# DDS_OUT_channel.net
KiCad netlist of a schematic drawn in Altium Designer
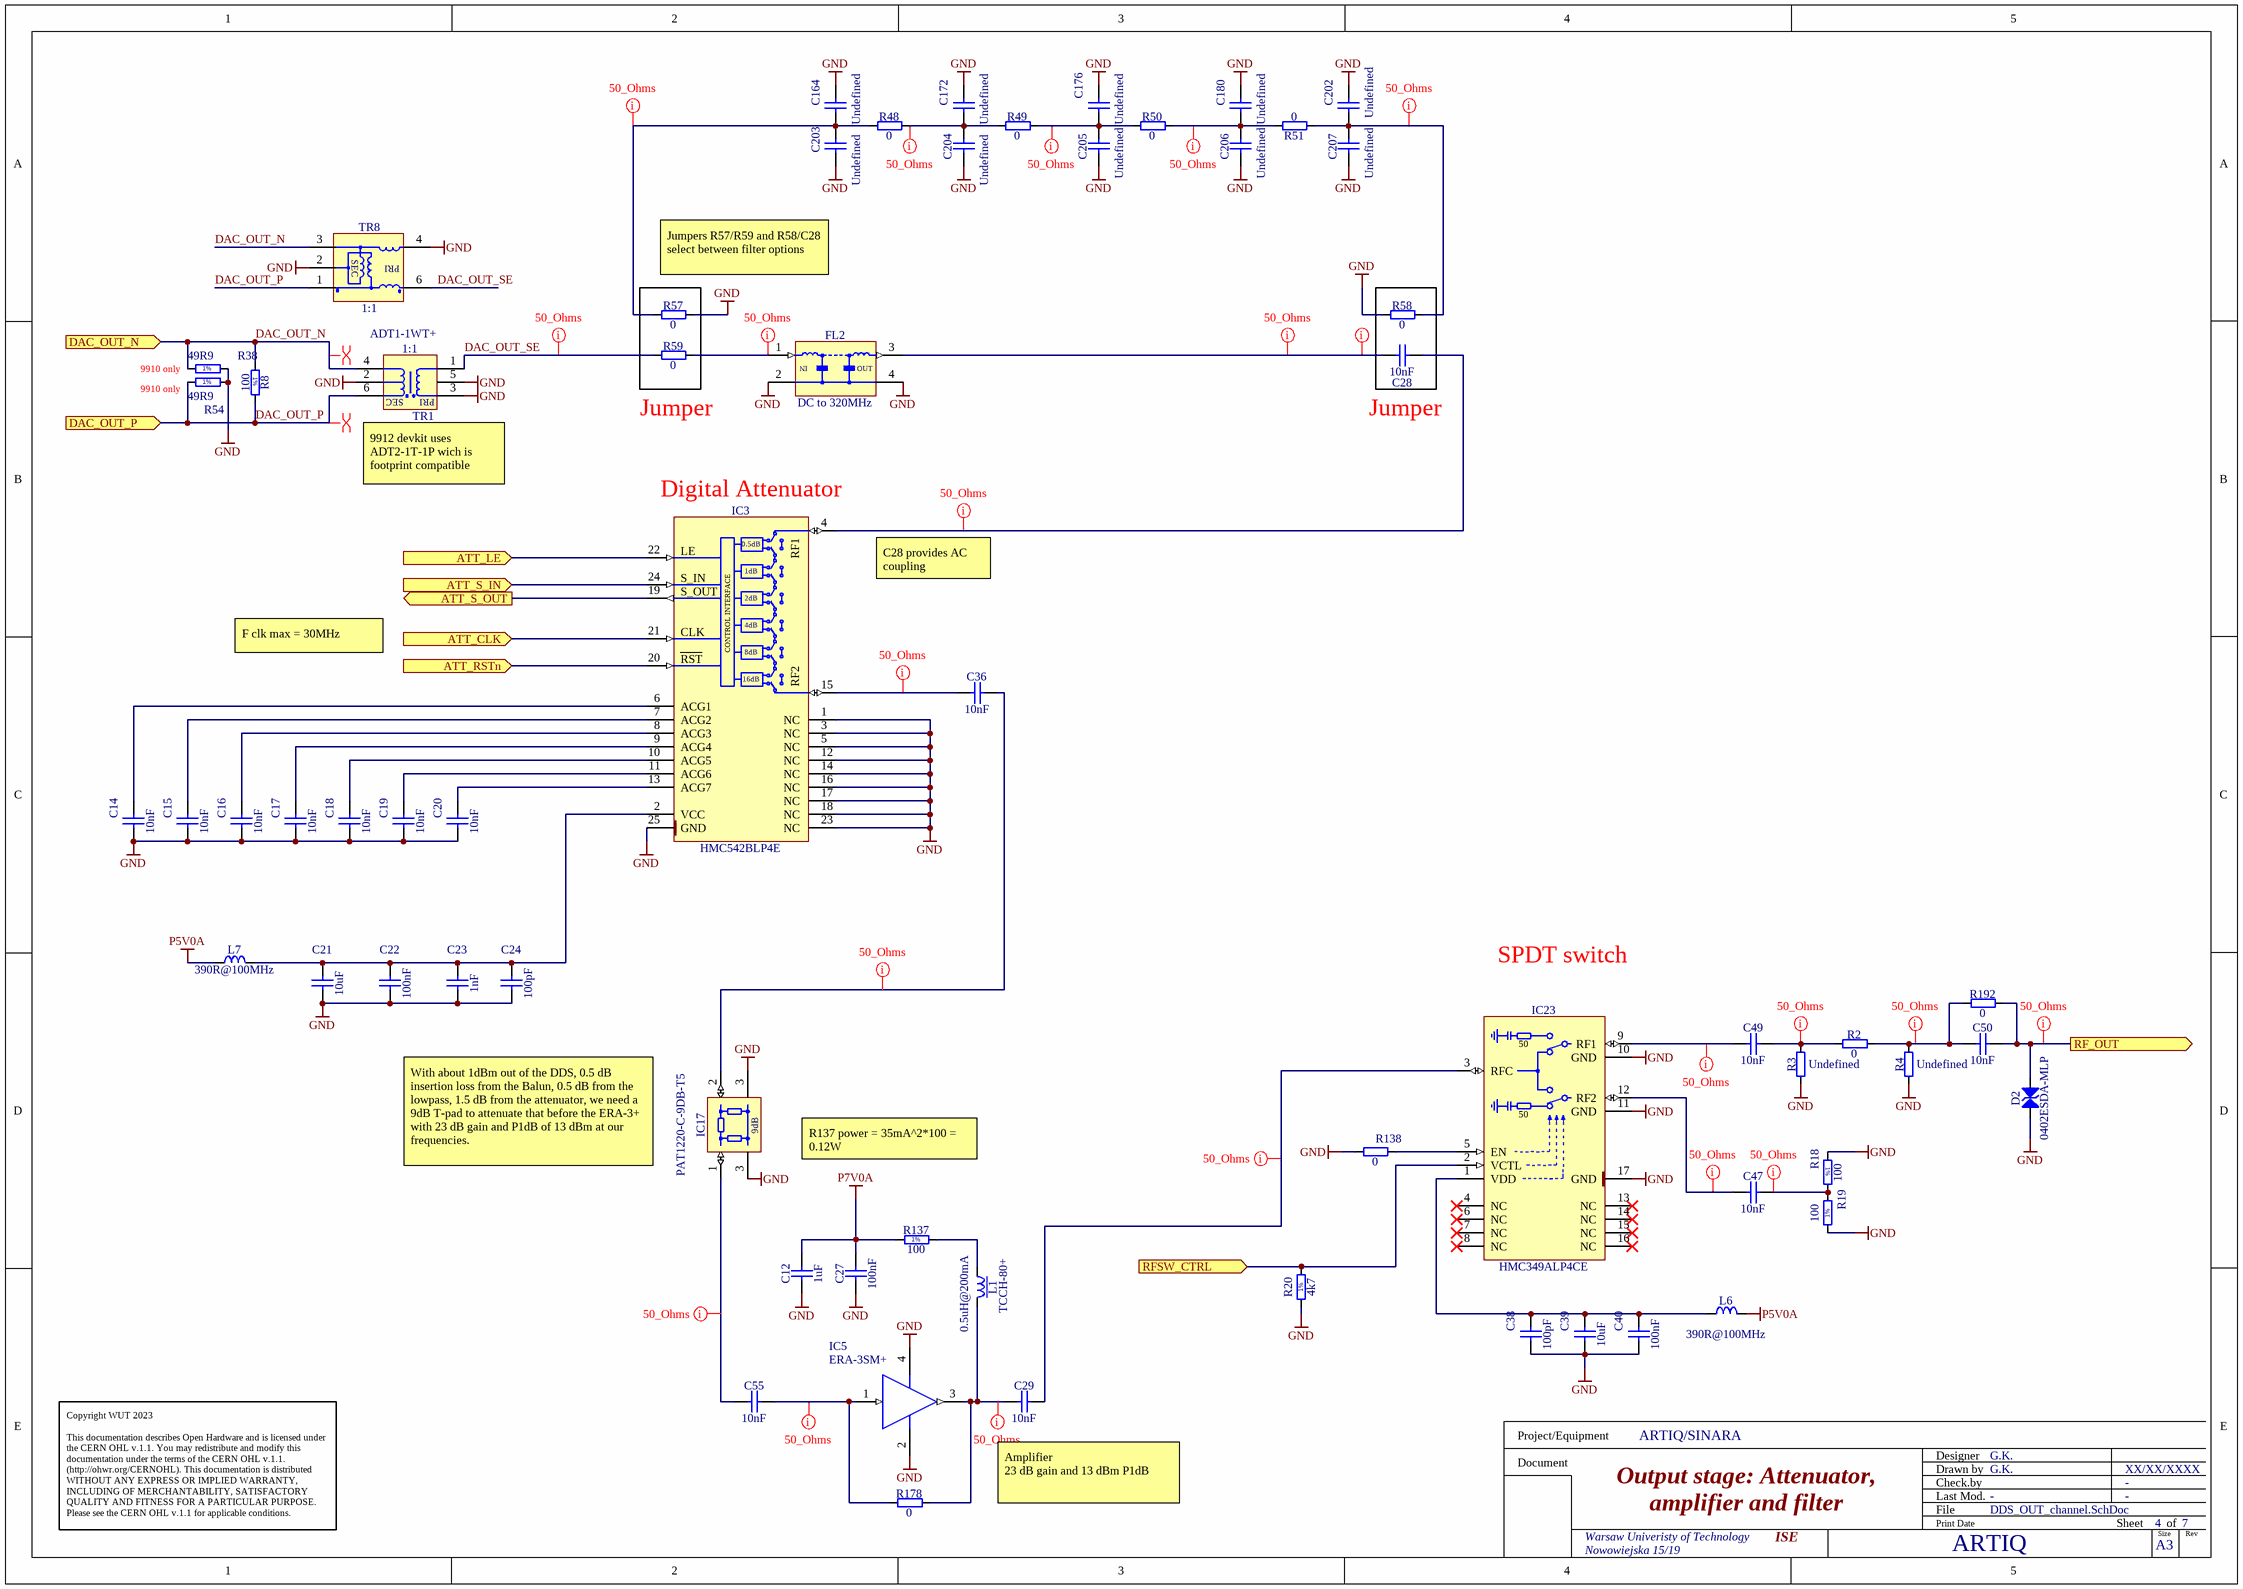
[diagram p0: DDS_OUT_channel.SchDoc]

(export (version "E")
  (design (tool "Eeschema 10.0.6"))
  (components
    (comp (ref "C12")
      (value "1uF")
      (footprint "CAPC2012X140N")
      (description "Non-polarised capacitor")
      (fields
        (field (name "PART NUMBER") "CC0805_1UF_35V_20%_X7R")
        (field (name "VOLTAGE") "35V")
        (field (name "AUTHOR") "CERN DEM JLC")
      )
      (libsource (lib "Capacitors") (part "Capacitor - non polarized"))
    )
    (comp (ref "C14")
      (value "10nF")
      (footprint "CAPC1005X55N")
      (description "Non-polarised capacitor")
      (fields
        (field (name "PART NUMBER") "CC0402_10NF_16V_10%_X7R")
        (field (name "VOLTAGE") "16V")
        (field (name "AUTHOR") "CERN DEM JLC")
      )
      (libsource (lib "Capacitors") (part "Capacitor - non polarized"))
    )
    (comp (ref "C15")
      (value "10nF")
      (footprint "CAPC1005X55N")
      (description "Non-polarised capacitor")
      (fields
        (field (name "PART NUMBER") "CC0402_10NF_16V_10%_X7R")
        (field (name "VOLTAGE") "16V")
        (field (name "AUTHOR") "CERN DEM JLC")
      )
      (libsource (lib "Capacitors") (part "Capacitor - non polarized"))
    )
    (comp (ref "C16")
      (value "10nF")
      (footprint "CAPC1005X55N")
      (description "Non-polarised capacitor")
      (fields
        (field (name "PART NUMBER") "CC0402_10NF_16V_10%_X7R")
        (field (name "VOLTAGE") "16V")
        (field (name "AUTHOR") "CERN DEM JLC")
      )
      (libsource (lib "Capacitors") (part "Capacitor - non polarized"))
    )
    (comp (ref "C17")
      (value "10nF")
      (footprint "CAPC1005X55N")
      (description "Non-polarised capacitor")
      (fields
        (field (name "PART NUMBER") "CC0402_10NF_16V_10%_X7R")
        (field (name "VOLTAGE") "16V")
        (field (name "AUTHOR") "CERN DEM JLC")
      )
      (libsource (lib "Capacitors") (part "Capacitor - non polarized"))
    )
    (comp (ref "C18")
      (value "10nF")
      (footprint "CAPC1005X55N")
      (description "Non-polarised capacitor")
      (fields
        (field (name "PART NUMBER") "CC0402_10NF_16V_10%_X7R")
        (field (name "VOLTAGE") "16V")
        (field (name "AUTHOR") "CERN DEM JLC")
      )
      (libsource (lib "Capacitors") (part "Capacitor - non polarized"))
    )
    (comp (ref "C19")
      (value "10nF")
      (footprint "CAPC1005X55N")
      (description "Non-polarised capacitor")
      (fields
        (field (name "PART NUMBER") "CC0402_10NF_16V_10%_X7R")
        (field (name "VOLTAGE") "16V")
        (field (name "AUTHOR") "CERN DEM JLC")
      )
      (libsource (lib "Capacitors") (part "Capacitor - non polarized"))
    )
    (comp (ref "C20")
      (value "10nF")
      (footprint "CAPC1005X55N")
      (description "Non-polarised capacitor")
      (fields
        (field (name "PART NUMBER") "CC0402_10NF_16V_10%_X7R")
        (field (name "VOLTAGE") "16V")
        (field (name "AUTHOR") "CERN DEM JLC")
      )
      (libsource (lib "Capacitors") (part "Capacitor - non polarized"))
    )
    (comp (ref "C21")
      (value "10uF")
      (footprint "CAPC1608X80N")
      (description "Non-polarised capacitor")
      (fields
        (field (name "PART NUMBER") "CC0603_10UF_16V_20%_X5R")
        (field (name "VOLTAGE") "16V")
        (field (name "AUTHOR") "CERN DEM MR")
      )
      (libsource (lib "Capacitors") (part "Capacitor - non polarized"))
    )
    (comp (ref "C22")
      (value "100nF")
      (footprint "CAPC1005X55N")
      (description "Non-polarised capacitor")
      (fields
        (field (name "PART NUMBER") "CC0402_100NF_16V_10%_X7R")
        (field (name "VOLTAGE") "16V")
        (field (name "AUTHOR") "CERN DEM JLC")
      )
      (libsource (lib "Capacitors") (part "Capacitor - non polarized"))
    )
    (comp (ref "C23")
      (value "1nF")
      (footprint "CAPC1005X55N")
      (description "Non-polarised capacitor")
      (fields
        (field (name "PART NUMBER") "CC0402_1NF_50V_10%_X7R")
        (field (name "VOLTAGE") "50V")
        (field (name "AUTHOR") "CERN DEM JLC")
      )
      (libsource (lib "Capacitors") (part "Capacitor - non polarized"))
    )
    (comp (ref "C24")
      (value "100pF")
      (footprint "CAPC1005X55N")
      (description "Non-polarised capacitor")
      (fields
        (field (name "PART NUMBER") "CC0402_100PF_50V_5%_C0G")
        (field (name "VOLTAGE") "50V")
        (field (name "AUTHOR") "CERN DEM JLC")
      )
      (libsource (lib "Capacitors") (part "Capacitor - non polarized"))
    )
    (comp (ref "C27")
      (value "100nF")
      (footprint "CAPC1005X55N")
      (description "Non-polarised capacitor")
      (fields
        (field (name "PART NUMBER") "CC0402_100NF_16V_10%_X5R")
        (field (name "VOLTAGE") "16V")
        (field (name "AUTHOR") "CERN DEM JLC")
      )
      (libsource (lib "Capacitors") (part "Capacitor - non polarized"))
    )
    (comp (ref "C28")
      (value "10nF")
      (footprint "CAPC1005X55N")
      (description "Non-polarised capacitor")
      (fields
        (field (name "PART NUMBER") "CC0402_10NF_16V_10%_X7R")
        (field (name "VOLTAGE") "16V")
        (field (name "AUTHOR") "CERN DEM JLC")
      )
      (libsource (lib "Capacitors") (part "Capacitor - non polarized"))
    )
    (comp (ref "C29")
      (value "10nF")
      (footprint "CAPC1005X55N")
      (description "Non-polarised capacitor")
      (fields
        (field (name "PART NUMBER") "CC0402_10NF_16V_10%_X7R")
        (field (name "VOLTAGE") "16V")
        (field (name "AUTHOR") "CERN DEM JLC")
      )
      (libsource (lib "Capacitors") (part "Capacitor - non polarized"))
    )
    (comp (ref "C36")
      (value "10nF")
      (footprint "CAPC1005X55N")
      (description "Non-polarised capacitor")
      (fields
        (field (name "PART NUMBER") "CC0402_10NF_16V_10%_X7R")
        (field (name "VOLTAGE") "16V")
        (field (name "AUTHOR") "CERN DEM JLC")
      )
      (libsource (lib "Capacitors") (part "Capacitor - non polarized"))
    )
    (comp (ref "C38")
      (value "100pF")
      (footprint "CAPC1005X55N")
      (description "Non-polarised capacitor")
      (fields
        (field (name "PART NUMBER") "CC0402_100PF_50V_5%_C0G")
        (field (name "VOLTAGE") "50V")
        (field (name "AUTHOR") "CERN DEM JLC")
      )
      (libsource (lib "Capacitors") (part "Capacitor - non polarized"))
    )
    (comp (ref "C39")
      (value "10uF")
      (footprint "CAPC1608X80N")
      (description "Non-polarised capacitor")
      (fields
        (field (name "PART NUMBER") "CC0603_10UF_16V_20%_X5R")
        (field (name "VOLTAGE") "16V")
        (field (name "AUTHOR") "CERN DEM MR")
      )
      (libsource (lib "Capacitors") (part "Capacitor - non polarized"))
    )
    (comp (ref "C40")
      (value "100nF")
      (footprint "CAPC1005X55N")
      (description "Non-polarised capacitor")
      (fields
        (field (name "PART NUMBER") "CC0402_100NF_16V_10%_X5R")
        (field (name "VOLTAGE") "16V")
        (field (name "AUTHOR") "CERN DEM JLC")
      )
      (libsource (lib "Capacitors") (part "Capacitor - non polarized"))
    )
    (comp (ref "C47")
      (value "10nF")
      (footprint "CAPC1005X55N")
      (description "Non-polarised capacitor")
      (fields
        (field (name "PART NUMBER") "CC0402_10NF_16V_10%_X7R")
        (field (name "VOLTAGE") "16V")
        (field (name "AUTHOR") "CERN DEM JLC")
      )
      (libsource (lib "Capacitors") (part "Capacitor - non polarized"))
    )
    (comp (ref "C49")
      (value "10nF")
      (footprint "CAPC1005X55N")
      (description "Non-polarised capacitor")
      (fields
        (field (name "PART NUMBER") "CC0402_10NF_16V_10%_X7R")
        (field (name "VOLTAGE") "16V")
        (field (name "AUTHOR") "CERN DEM JLC")
      )
      (libsource (lib "Capacitors") (part "Capacitor - non polarized"))
    )
    (comp (ref "C50")
      (value "10nF")
      (footprint "CAPC1005X55N")
      (description "Non-polarised capacitor")
      (fields
        (field (name "PART NUMBER") "CC0402_10NF_16V_10%_X7R")
        (field (name "VOLTAGE") "16V")
        (field (name "AUTHOR") "CERN DEM JLC")
      )
      (libsource (lib "Capacitors") (part "Capacitor - non polarized"))
    )
    (comp (ref "C55")
      (value "10nF")
      (footprint "CAPC1005X55N")
      (description "Non-polarised capacitor")
      (fields
        (field (name "PART NUMBER") "CC0402_10NF_16V_10%_X7R")
        (field (name "VOLTAGE") "16V")
        (field (name "AUTHOR") "CERN DEM JLC")
      )
      (libsource (lib "Capacitors") (part "Capacitor - non polarized"))
    )
    (comp (ref "C164")
      (value "Undefined")
      (footprint "CAPC1005X55N")
      (description "Non-polarised capacitor")
      (fields (field (name "PART NUMBER") "CC0402_NO-VALUE") (field (name "AUTHOR") "CERN DEM JLC"))
      (libsource (lib "Capacitors") (part "Capacitor - non polarized"))
    )
    (comp (ref "C172")
      (value "Undefined")
      (footprint "CAPC1005X55N")
      (description "Non-polarised capacitor")
      (fields (field (name "PART NUMBER") "CC0402_NO-VALUE") (field (name "AUTHOR") "CERN DEM JLC"))
      (libsource (lib "Capacitors") (part "Capacitor - non polarized"))
    )
    (comp (ref "C176")
      (value "Undefined")
      (footprint "CAPC1005X55N")
      (description "Non-polarised capacitor")
      (fields (field (name "PART NUMBER") "CC0402_NO-VALUE") (field (name "AUTHOR") "CERN DEM JLC"))
      (libsource (lib "Capacitors") (part "Capacitor - non polarized"))
    )
    (comp (ref "C180")
      (value "Undefined")
      (footprint "CAPC1005X55N")
      (description "Non-polarised capacitor")
      (fields (field (name "PART NUMBER") "CC0402_NO-VALUE") (field (name "AUTHOR") "CERN DEM JLC"))
      (libsource (lib "Capacitors") (part "Capacitor - non polarized"))
    )
    (comp (ref "C202")
      (value "Undefined")
      (footprint "CAPC1005X55N")
      (description "Non-polarised capacitor")
      (fields (field (name "PART NUMBER") "CC0402_NO-VALUE") (field (name "AUTHOR") "CERN DEM JLC"))
      (libsource (lib "Capacitors") (part "Capacitor - non polarized"))
    )
    (comp (ref "C203")
      (value "Undefined")
      (footprint "CAPC1005X55N")
      (description "Non-polarised capacitor")
      (fields (field (name "PART NUMBER") "CC0402_NO-VALUE") (field (name "AUTHOR") "CERN DEM JLC"))
      (libsource (lib "Capacitors") (part "Capacitor - non polarized"))
    )
    (comp (ref "C204")
      (value "Undefined")
      (footprint "CAPC1005X55N")
      (description "Non-polarised capacitor")
      (fields (field (name "PART NUMBER") "CC0402_NO-VALUE") (field (name "AUTHOR") "CERN DEM JLC"))
      (libsource (lib "Capacitors") (part "Capacitor - non polarized"))
    )
    (comp (ref "C205")
      (value "Undefined")
      (footprint "CAPC1005X55N")
      (description "Non-polarised capacitor")
      (fields (field (name "PART NUMBER") "CC0402_NO-VALUE") (field (name "AUTHOR") "CERN DEM JLC"))
      (libsource (lib "Capacitors") (part "Capacitor - non polarized"))
    )
    (comp (ref "C206")
      (value "Undefined")
      (footprint "CAPC1005X55N")
      (description "Non-polarised capacitor")
      (fields (field (name "PART NUMBER") "CC0402_NO-VALUE") (field (name "AUTHOR") "CERN DEM JLC"))
      (libsource (lib "Capacitors") (part "Capacitor - non polarized"))
    )
    (comp (ref "C207")
      (value "Undefined")
      (footprint "CAPC1005X55N")
      (description "Non-polarised capacitor")
      (fields (field (name "PART NUMBER") "CC0402_NO-VALUE") (field (name "AUTHOR") "CERN DEM JLC"))
      (libsource (lib "Capacitors") (part "Capacitor - non polarized"))
    )
    (comp (ref "D2")
      (value "0402ESDA-MLP")
      (footprint "EATON_0402ESDA-MLP")
      (description "Transient Voltage Suppressor Diode (Bi-Directional)")
      (fields
        (field (name "VOLTAGE") "8kV")
        (field (name "MANUFACTURER") "EATON")
        (field (name "AUTHOR") "CERN DEM MR")
      )
      (libsource (lib "ICs And Semiconductors") (part "Diode TVS Bi-Directional"))
    )
    (comp (ref "FL2")
      (value "DC to 320MHz")
      (footprint "FIL_MINI-CIRCUITS_FV1206")
      (description "50 Ohm DC to 320MHz Low Pass Filter")
      (fields
        (field (name "PART NUMBER") "FIL_MINI-CIRCUITS_LFCN-320")
        (field (name "MANUFACTURER") "MINI-CIRCUITS")
        (field (name "AUTHOR") "CERN DEM JLC")
      )
      (libsource (lib "LIBRARY_SCH") (part "FIL_MINI-CIRCUITS_LFCN-320"))
    )
    (comp (ref "IC3")
      (value "HMC542BLP4E")
      (footprint "QFN50P400X400X100-25N-S295")
      (description "0.5dB LSB GaAs MMIC 6-bit Digital Serial Control Attenuator, DC - 4GHz")
      (fields (field (name "MANUFACTURER") "HITTITE MICROWAVE CORP") (field (name "AUTHOR") "CERN DEM JMW"))
      (libsource (lib "ICs And Semiconductors") (part "HMC542BLP4E"))
    )
    (comp (ref "IC5")
      (value "ERA-3SM+")
      (footprint "MINI-CIRCUITS_WW107")
      (description "DC-3GHz Monolithic Amplifier")
      (fields (field (name "MANUFACTURER") "MINI-CIRCUITS") (field (name "AUTHOR") "GK"))
      (libsource (lib "LIBRARY_SCH") (part "RF_ERA-3SM+"))
    )
    (comp (ref "IC17")
      (value "PAT1220-C-9DB-T5")
      (footprint "SUSUMU_PAT1220")
      (description "DC to 10GHz, 100mw, 50 Ohm, 9dB, Precision chip attenuator")
      (fields (field (name "MANUFACTURER") "SUSUMU") (field (name "AUTHOR") "GK"))
      (libsource (lib "LIBRARY_SCH") (part "RF_PAT1220-C-9DB-T5"))
    )
    (comp (ref "IC23")
      (value "HMC349ALP4CE")
      (footprint "QFN65P400X400X100-17N-S255")
      (description "DC-4GHz High Isolation SPDT Non-Reflective Switch")
      (fields (field (name "MANUFACTURER") "ANALOG DEVICES") (field (name "AUTHOR") "CERN DEM JLC"))
      (libsource (lib "ICs And Semiconductors") (part "HMC349ALP4CE"))
    )
    (comp (ref "L1")
      (value "0.5uH@200mA")
      (footprint "IND_MINI-CIRCUITS_GU1604")
      (description "50 Ohms, 50 to 8200 MHz RF Choke")
      (fields
        (field (name "PART NUMBER") "IND_MINI-CIRCUITS_TCCH-80+")
        (field (name "POWER") "200mA")
        (field (name "MANUFACTURER PART NUMBER") "TCCH-80+")
        (field (name "AUTHOR") "CERN DEM JLC")
      )
      (libsource (lib "Inductors & Transformers") (part "IND_MINI-CIRCUITS_TCCH-80+"))
    )
    (comp (ref "L6")
      (value "390R@100MHz")
      (footprint "INDC1608X95N")
      (description "Inductor")
      (fields
        (field (name "PART NUMBER") "IND0603_TDK_MPZ1608R391A")
        (field (name "POWER") "1.2A")
        (field (name "AUTHOR") "CERN DEM JLC")
      )
      (libsource (lib "Inductors & Transformers") (part "Inductor"))
    )
    (comp (ref "L7")
      (value "390R@100MHz")
      (footprint "INDC1608X95N")
      (description "Inductor")
      (fields
        (field (name "PART NUMBER") "IND0603_TDK_MPZ1608R391A")
        (field (name "POWER") "1.2A")
        (field (name "AUTHOR") "CERN DEM JLC")
      )
      (libsource (lib "Inductors & Transformers") (part "Inductor"))
    )
    (comp (ref "R2")
      (value "0")
      (footprint "RESC1005X40N")
      (description "Resistor")
      (fields
        (field (name "PART NUMBER") "R0402_0R_JUMPER")
        (field (name "MANUFACTURER") "GENERIC")
        (field (name "AUTHOR") "CERN DEM JLC")
      )
      (libsource (lib "Resistors") (part "Resistor"))
    )
    (comp (ref "R3")
      (value "Undefined")
      (footprint "RESC1005X40N")
      (description "Resistor")
      (fields (field (name "PART NUMBER") "R0402_NO-VALUE") (field (name "AUTHOR") "CERN DEM JLC"))
      (libsource (lib "Resistors") (part "Resistor"))
    )
    (comp (ref "R4")
      (value "Undefined")
      (footprint "RESC1005X40N")
      (description "Resistor")
      (fields (field (name "PART NUMBER") "R0402_NO-VALUE") (field (name "AUTHOR") "CERN DEM JLC"))
      (libsource (lib "Resistors") (part "Resistor"))
    )
    (comp (ref "R8")
      (value "100")
      (footprint "RESC1005X40N")
      (description "Resistor - 1%")
      (fields
        (field (name "PART NUMBER") "R0402_100R_1%_0.0625W_100PPM")
        (field (name "POWER") "0.0625W")
        (field (name "AUTHOR") "CERN DEM JLC")
      )
      (libsource (lib "Resistors") (part "Resistor - 1%"))
    )
    (comp (ref "R18")
      (value "100")
      (footprint "RESC1005X40N")
      (description "Resistor - 1%")
      (fields
        (field (name "PART NUMBER") "R0402_100R_1%_0.0625W_100PPM")
        (field (name "POWER") "0.0625W")
        (field (name "AUTHOR") "CERN DEM JLC")
      )
      (libsource (lib "Resistors") (part "Resistor - 1%"))
    )
    (comp (ref "R19")
      (value "100")
      (footprint "RESC1005X40N")
      (description "Resistor - 1%")
      (fields
        (field (name "PART NUMBER") "R0402_100R_1%_0.0625W_100PPM")
        (field (name "POWER") "0.0625W")
        (field (name "AUTHOR") "CERN DEM JLC")
      )
      (libsource (lib "Resistors") (part "Resistor - 1%"))
    )
    (comp (ref "R20")
      (value "4k7")
      (footprint "RESC1005X40N")
      (description "Resistor - 1%")
      (fields
        (field (name "PART NUMBER") "R0402_4K7_1%_0.0625W_100PPM")
        (field (name "POWER") "0.0625W")
        (field (name "AUTHOR") "CERN DEM JLC")
      )
      (libsource (lib "Resistors") (part "Resistor - 1%"))
    )
    (comp (ref "R38")
      (value "49R9")
      (footprint "RESC1005X40N")
      (description "Resistor - 1%")
      (fields
        (field (name "PART NUMBER") "R0402_49R9_1%_0.0625W_100PPM")
        (field (name "POWER") "0.0625W")
        (field (name "AUTHOR") "CERN DEM JLC")
      )
      (libsource (lib "Resistors") (part "Resistor - 1%"))
    )
    (comp (ref "R48")
      (value "0")
      (footprint "RESC1005X40N")
      (description "Resistor")
      (fields
        (field (name "PART NUMBER") "R0402_0R_JUMPER")
        (field (name "MANUFACTURER") "GENERIC")
        (field (name "AUTHOR") "CERN DEM JLC")
      )
      (libsource (lib "Resistors") (part "Resistor"))
    )
    (comp (ref "R49")
      (value "0")
      (footprint "RESC1005X40N")
      (description "Resistor")
      (fields
        (field (name "PART NUMBER") "R0402_0R_JUMPER")
        (field (name "MANUFACTURER") "GENERIC")
        (field (name "AUTHOR") "CERN DEM JLC")
      )
      (libsource (lib "Resistors") (part "Resistor"))
    )
    (comp (ref "R50")
      (value "0")
      (footprint "RESC1005X40N")
      (description "Resistor")
      (fields
        (field (name "PART NUMBER") "R0402_0R_JUMPER")
        (field (name "MANUFACTURER") "GENERIC")
        (field (name "AUTHOR") "CERN DEM JLC")
      )
      (libsource (lib "Resistors") (part "Resistor"))
    )
    (comp (ref "R51")
      (value "0")
      (footprint "RESC1005X40N")
      (description "Resistor")
      (fields
        (field (name "PART NUMBER") "R0402_0R_JUMPER")
        (field (name "MANUFACTURER") "GENERIC")
        (field (name "AUTHOR") "CERN DEM JLC")
      )
      (libsource (lib "Resistors") (part "Resistor"))
    )
    (comp (ref "R54")
      (value "49R9")
      (footprint "RESC1005X40N")
      (description "Resistor - 1%")
      (fields
        (field (name "PART NUMBER") "R0402_49R9_1%_0.0625W_100PPM")
        (field (name "POWER") "0.0625W")
        (field (name "AUTHOR") "CERN DEM JLC")
      )
      (libsource (lib "Resistors") (part "Resistor - 1%"))
    )
    (comp (ref "R57")
      (value "0")
      (footprint "RESC1005X40N")
      (description "Resistor")
      (fields
        (field (name "PART NUMBER") "R0402_0R_JUMPER")
        (field (name "MANUFACTURER") "GENERIC")
        (field (name "AUTHOR") "CERN DEM JLC")
      )
      (libsource (lib "Resistors") (part "Resistor"))
    )
    (comp (ref "R58")
      (value "0")
      (footprint "RESC1005X40N")
      (description "Resistor")
      (fields
        (field (name "PART NUMBER") "R0402_0R_JUMPER")
        (field (name "MANUFACTURER") "GENERIC")
        (field (name "AUTHOR") "CERN DEM JLC")
      )
      (libsource (lib "Resistors") (part "Resistor"))
    )
    (comp (ref "R59")
      (value "0")
      (footprint "RESC1005X40N")
      (description "Resistor")
      (fields
        (field (name "PART NUMBER") "R0402_0R_JUMPER")
        (field (name "MANUFACTURER") "GENERIC")
        (field (name "AUTHOR") "CERN DEM JLC")
      )
      (libsource (lib "Resistors") (part "Resistor"))
    )
    (comp (ref "R137")
      (value "100")
      (footprint "RESC3216X65N")
      (description "Resistor - 1%")
      (fields
        (field (name "PART NUMBER") "R1206_100R_1%_0.5W_100PPM_VISHAY_CRCW-HP e3")
        (field (name "POWER") "0.5W")
        (field (name "AUTHOR") "CERN DEM JLC")
      )
      (libsource (lib "Resistors") (part "Resistor - 1%"))
    )
    (comp (ref "R138")
      (value "0")
      (footprint "RESC1005X40N")
      (description "Resistor")
      (fields
        (field (name "PART NUMBER") "R0402_0R_JUMPER")
        (field (name "MANUFACTURER") "GENERIC")
        (field (name "AUTHOR") "CERN DEM JLC")
      )
      (libsource (lib "Resistors") (part "Resistor"))
    )
    (comp (ref "R178")
      (value "0")
      (footprint "RESC1608X55N")
      (description "Resistor")
      (fields
        (field (name "PART NUMBER") "R0603_0R_JUMPER")
        (field (name "MANUFACTURER") "GENERIC")
        (field (name "AUTHOR") "CERN DEM JLC")
      )
      (libsource (lib "Resistors") (part "Resistor"))
    )
    (comp (ref "R192")
      (value "0")
      (footprint "RESC1005X40N")
      (description "Resistor")
      (fields
        (field (name "PART NUMBER") "R0402_0R_JUMPER")
        (field (name "MANUFACTURER") "GENERIC")
        (field (name "AUTHOR") "CERN DEM JLC")
      )
      (libsource (lib "Resistors") (part "Resistor"))
    )
    (comp (ref "TR1")
      (value "1:1")
      (footprint "XFMR_MINI-CIRCUITS_CD542")
      (description "75 Ohm 0.4 To 800MHz RF Transformers")
      (fields
        (field (name "PART NUMBER") "XFMR_MINI-CIRCUITS_ADT1-1WT+")
        (field (name "MANUFACTURER") "MINI-CIRCUITS")
        (field (name "MANUFACTURER PART NUMBER") "ADT1-1WT+")
        (field (name "AUTHOR") "CERN DEM JLC")
      )
      (libsource (lib "Inductors & Transformers") (part "XFMR_MINI-CIRCUITS_ADT1-1WT+"))
    )
    (comp (ref "TR8")
      (value "1:1")
      (footprint "XFMR_MINI-CIRCUITS_AT1521")
      (description "50 Ohms 5 To 1500MHz TLT RF Transformer")
      (fields
        (field (name "PART NUMBER") "XFMR_MINI-CIRCUITS_TC1-1T-152X+")
        (field (name "MANUFACTURER") "MINI-CIRCUITS")
        (field (name "AUTHOR") "GK")
      )
      (libsource (lib "Inductors_Transformers") (part "XFMR_MINI-CIRCUITS_TC1-1T-152X+"))
    )
  )
  (nets
    (net (code "1") (name "/ATT_CLK") (class "Default")
      (node (ref "IC3") (pin "21") (pinfunction "SHIFT_CLOCK_21") (pintype "input"))
    )
    (net (code "2") (name "/ATT_LE") (class "Default")
      (node (ref "IC3") (pin "22") (pinfunction "LATCH_ENABLE_22") (pintype "input"))
    )
    (net (code "3") (name "/ATT_RSTn") (class "Default")
      (node (ref "IC3") (pin "20") (pinfunction "~{RESET}_20") (pintype "input"))
    )
    (net (code "4") (name "/ATT_S_IN") (class "Default")
      (node (ref "IC3") (pin "24") (pinfunction "SERIAL_INPUT_24") (pintype "input"))
    )
    (net (code "5") (name "/ATT_S_OUT") (class "Default")
      (node (ref "IC3") (pin "19") (pinfunction "SERIAL_OUTPUT_19") (pintype "output"))
    )
    (net (code "6") (name "/DAC_OUT_N") (class "Default")
      (node (ref "R38") (pin "1") (pinfunction "1_1") (pintype "passive"))
      (node (ref "R8") (pin "1") (pinfunction "1_1") (pintype "passive"))
      (node (ref "TR1") (pin "4") (pinfunction "S_4") (pintype "passive"))
      (node (ref "TR8") (pin "3") (pinfunction "S_3") (pintype "passive"))
    )
    (net (code "7") (name "/DAC_OUT_P") (class "Default")
      (node (ref "R54") (pin "1") (pinfunction "1_1") (pintype "passive"))
      (node (ref "R8") (pin "2") (pinfunction "2_2") (pintype "passive"))
      (node (ref "TR1") (pin "6") (pinfunction "SDOT_6") (pintype "passive"))
      (node (ref "TR8") (pin "1") (pinfunction "SDOT_1") (pintype "passive"))
    )
    (net (code "8") (name "/DAC_OUT_SE") (class "Default")
      (node (ref "R59") (pin "1") (pinfunction "1_1") (pintype "passive"))
      (node (ref "TR1") (pin "1") (pinfunction "P_1") (pintype "passive"))
      (node (ref "TR8") (pin "6") (pinfunction "PDOT_6") (pintype "passive"))
    )
    (net (code "9") (name "/RFSW_CTRL") (class "Default")
      (node (ref "IC23") (pin "2") (pinfunction "VCTL_2") (pintype "input"))
      (node (ref "R20") (pin "2") (pinfunction "2_2") (pintype "passive"))
    )
    (net (code "10") (name "/RF_OUT") (class "Default")
      (node (ref "C50") (pin "2") (pinfunction "2_2") (pintype "passive"))
      (node (ref "D2") (pin "2") (pinfunction "2_2") (pintype "passive"))
      (node (ref "R192") (pin "2") (pinfunction "2_2") (pintype "passive"))
    )
    (net (code "11") (name "GND") (class "Default")
      (node (ref "C12") (pin "1") (pinfunction "1_1") (pintype "passive"))
      (node (ref "C14") (pin "1") (pinfunction "1_1") (pintype "passive"))
      (node (ref "C15") (pin "1") (pinfunction "1_1") (pintype "passive"))
      (node (ref "C16") (pin "1") (pinfunction "1_1") (pintype "passive"))
      (node (ref "C164") (pin "2") (pinfunction "2_2") (pintype "passive"))
      (node (ref "C17") (pin "1") (pinfunction "1_1") (pintype "passive"))
      (node (ref "C172") (pin "2") (pinfunction "2_2") (pintype "passive"))
      (node (ref "C176") (pin "2") (pinfunction "2_2") (pintype "passive"))
      (node (ref "C18") (pin "1") (pinfunction "1_1") (pintype "passive"))
      (node (ref "C180") (pin "2") (pinfunction "2_2") (pintype "passive"))
      (node (ref "C19") (pin "1") (pinfunction "1_1") (pintype "passive"))
      (node (ref "C20") (pin "1") (pinfunction "1_1") (pintype "passive"))
      (node (ref "C202") (pin "2") (pinfunction "2_2") (pintype "passive"))
      (node (ref "C203") (pin "1") (pinfunction "1_1") (pintype "passive"))
      (node (ref "C204") (pin "1") (pinfunction "1_1") (pintype "passive"))
      (node (ref "C205") (pin "1") (pinfunction "1_1") (pintype "passive"))
      (node (ref "C206") (pin "1") (pinfunction "1_1") (pintype "passive"))
      (node (ref "C207") (pin "1") (pinfunction "1_1") (pintype "passive"))
      (node (ref "C21") (pin "1") (pinfunction "1_1") (pintype "passive"))
      (node (ref "C22") (pin "1") (pinfunction "1_1") (pintype "passive"))
      (node (ref "C23") (pin "1") (pinfunction "1_1") (pintype "passive"))
      (node (ref "C24") (pin "1") (pinfunction "1_1") (pintype "passive"))
      (node (ref "C27") (pin "1") (pinfunction "1_1") (pintype "passive"))
      (node (ref "C38") (pin "2") (pinfunction "2_2") (pintype "passive"))
      (node (ref "C39") (pin "1") (pinfunction "1_1") (pintype "passive"))
      (node (ref "C40") (pin "1") (pinfunction "1_1") (pintype "passive"))
      (node (ref "D2") (pin "1") (pinfunction "1_1") (pintype "passive"))
      (node (ref "FL2") (pin "2") (pinfunction "GND_2") (pintype "power_in"))
      (node (ref "FL2") (pin "4") (pinfunction "GND_4") (pintype "power_in"))
      (node (ref "IC17") (pin "3") (pinfunction "GND_3") (pintype "passive"))
      (node (ref "IC23") (pin "10") (pinfunction "GND_10") (pintype "power_in"))
      (node (ref "IC23") (pin "11") (pinfunction "GND_11") (pintype "power_in"))
      (node (ref "IC23") (pin "17") (pinfunction "GND_17") (pintype "power_in"))
      (node (ref "IC3") (pin "1") (pinfunction "NC_1") (pintype "passive"))
      (node (ref "IC3") (pin "12") (pinfunction "NC_12") (pintype "passive"))
      (node (ref "IC3") (pin "14") (pinfunction "NC_14") (pintype "passive"))
      (node (ref "IC3") (pin "16") (pinfunction "NC_16") (pintype "passive"))
      (node (ref "IC3") (pin "17") (pinfunction "NC_17") (pintype "passive"))
      (node (ref "IC3") (pin "18") (pinfunction "NC_18") (pintype "passive"))
      (node (ref "IC3") (pin "23") (pinfunction "NC_23") (pintype "passive"))
      (node (ref "IC3") (pin "25") (pinfunction "GND_25") (pintype "power_in"))
      (node (ref "IC3") (pin "3") (pinfunction "NC_3") (pintype "passive"))
      (node (ref "IC3") (pin "5") (pinfunction "NC_5") (pintype "passive"))
      (node (ref "IC5") (pin "2") (pinfunction "GND_2") (pintype "power_in"))
      (node (ref "IC5") (pin "4") (pinfunction "GND_4") (pintype "power_in"))
      (node (ref "R138") (pin "1") (pinfunction "1_1") (pintype "passive"))
      (node (ref "R18") (pin "1") (pinfunction "1_1") (pintype "passive"))
      (node (ref "R19") (pin "1") (pinfunction "1_1") (pintype "passive"))
      (node (ref "R20") (pin "1") (pinfunction "1_1") (pintype "passive"))
      (node (ref "R3") (pin "1") (pinfunction "1_1") (pintype "passive"))
      (node (ref "R38") (pin "2") (pinfunction "2_2") (pintype "passive"))
      (node (ref "R4") (pin "1") (pinfunction "1_1") (pintype "passive"))
      (node (ref "R54") (pin "2") (pinfunction "2_2") (pintype "passive"))
      (node (ref "R57") (pin "2") (pinfunction "2_2") (pintype "passive"))
      (node (ref "R58") (pin "2") (pinfunction "2_2") (pintype "passive"))
      (node (ref "TR1") (pin "2") (pinfunction "SCT_2") (pintype "passive"))
      (node (ref "TR1") (pin "3") (pinfunction "PDOT_3") (pintype "passive"))
      (node (ref "TR1") (pin "5") (pinfunction "NC_5") (pintype "passive"))
      (node (ref "TR8") (pin "2") (pinfunction "SCT_2") (pintype "passive"))
      (node (ref "TR8") (pin "4") (pinfunction "P_4") (pintype "passive"))
    )
    (net (code "12") (name "Net-(C47-Pad2)") (class "Default")
      (node (ref "C47") (pin "2") (pinfunction "2_2") (pintype "passive"))
      (node (ref "R18") (pin "2") (pinfunction "2_2") (pintype "passive"))
      (node (ref "R19") (pin "2") (pinfunction "2_2") (pintype "passive"))
    )
    (net (code "13") (name "Net-(C49-Pad2)") (class "Default")
      (node (ref "C49") (pin "2") (pinfunction "2_2") (pintype "passive"))
      (node (ref "R2") (pin "1") (pinfunction "1_1") (pintype "passive"))
      (node (ref "R3") (pin "2") (pinfunction "2_2") (pintype "passive"))
    )
    (net (code "14") (name "Net-(C50-Pad1)") (class "Default")
      (node (ref "C50") (pin "1") (pinfunction "1_1") (pintype "passive"))
      (node (ref "R192") (pin "1") (pinfunction "1_1") (pintype "passive"))
      (node (ref "R2") (pin "2") (pinfunction "2_2") (pintype "passive"))
      (node (ref "R4") (pin "2") (pinfunction "2_2") (pintype "passive"))
    )
    (net (code "15") (name "Net-(C164-Pad1)") (class "Default")
      (node (ref "C164") (pin "1") (pinfunction "1_1") (pintype "passive"))
      (node (ref "C203") (pin "2") (pinfunction "2_2") (pintype "passive"))
      (node (ref "R48") (pin "1") (pinfunction "1_1") (pintype "passive"))
      (node (ref "R57") (pin "1") (pinfunction "1_1") (pintype "passive"))
    )
    (net (code "16") (name "Net-(C172-Pad1)") (class "Default")
      (node (ref "C172") (pin "1") (pinfunction "1_1") (pintype "passive"))
      (node (ref "C204") (pin "2") (pinfunction "2_2") (pintype "passive"))
      (node (ref "R48") (pin "2") (pinfunction "2_2") (pintype "passive"))
      (node (ref "R49") (pin "1") (pinfunction "1_1") (pintype "passive"))
    )
    (net (code "17") (name "Net-(C176-Pad1)") (class "Default")
      (node (ref "C176") (pin "1") (pinfunction "1_1") (pintype "passive"))
      (node (ref "C205") (pin "2") (pinfunction "2_2") (pintype "passive"))
      (node (ref "R49") (pin "2") (pinfunction "2_2") (pintype "passive"))
      (node (ref "R50") (pin "1") (pinfunction "1_1") (pintype "passive"))
    )
    (net (code "18") (name "Net-(C180-Pad1)") (class "Default")
      (node (ref "C180") (pin "1") (pinfunction "1_1") (pintype "passive"))
      (node (ref "C206") (pin "2") (pinfunction "2_2") (pintype "passive"))
      (node (ref "R50") (pin "2") (pinfunction "2_2") (pintype "passive"))
      (node (ref "R51") (pin "2") (pinfunction "2_2") (pintype "passive"))
    )
    (net (code "19") (name "Net-(C202-Pad1)") (class "Default")
      (node (ref "C202") (pin "1") (pinfunction "1_1") (pintype "passive"))
      (node (ref "C207") (pin "2") (pinfunction "2_2") (pintype "passive"))
      (node (ref "R51") (pin "1") (pinfunction "1_1") (pintype "passive"))
      (node (ref "R58") (pin "1") (pinfunction "1_1") (pintype "passive"))
    )
    (net (code "20") (name "Net-(FL2-RFIN)") (class "Default")
      (node (ref "FL2") (pin "1") (pinfunction "RFIN_1") (pintype "input"))
      (node (ref "R59") (pin "2") (pinfunction "2_2") (pintype "passive"))
    )
    (net (code "21") (name "Net-(FL2-RFOUT)") (class "Default")
      (node (ref "C28") (pin "1") (pinfunction "1_1") (pintype "passive"))
      (node (ref "FL2") (pin "3") (pinfunction "RFOUT_3") (pintype "output"))
    )
    (net (code "22") (name "Net-(IC3-ACG1)") (class "Default")
      (node (ref "C14") (pin "2") (pinfunction "2_2") (pintype "passive"))
      (node (ref "IC3") (pin "6") (pinfunction "ACG1_6") (pintype "passive"))
    )
    (net (code "23") (name "Net-(IC3-ACG2)") (class "Default")
      (node (ref "C15") (pin "2") (pinfunction "2_2") (pintype "passive"))
      (node (ref "IC3") (pin "7") (pinfunction "ACG2_7") (pintype "passive"))
    )
    (net (code "24") (name "Net-(IC3-ACG3)") (class "Default")
      (node (ref "C16") (pin "2") (pinfunction "2_2") (pintype "passive"))
      (node (ref "IC3") (pin "8") (pinfunction "ACG3_8") (pintype "passive"))
    )
    (net (code "25") (name "Net-(IC3-ACG4)") (class "Default")
      (node (ref "C17") (pin "2") (pinfunction "2_2") (pintype "passive"))
      (node (ref "IC3") (pin "9") (pinfunction "ACG4_9") (pintype "passive"))
    )
    (net (code "26") (name "Net-(IC3-ACG5)") (class "Default")
      (node (ref "C18") (pin "2") (pinfunction "2_2") (pintype "passive"))
      (node (ref "IC3") (pin "10") (pinfunction "ACG5_10") (pintype "passive"))
    )
    (net (code "27") (name "Net-(IC3-ACG6)") (class "Default")
      (node (ref "C19") (pin "2") (pinfunction "2_2") (pintype "passive"))
      (node (ref "IC3") (pin "11") (pinfunction "ACG6_11") (pintype "passive"))
    )
    (net (code "28") (name "Net-(IC3-ACG7)") (class "Default")
      (node (ref "C20") (pin "2") (pinfunction "2_2") (pintype "passive"))
      (node (ref "IC3") (pin "13") (pinfunction "ACG7_13") (pintype "passive"))
    )
    (net (code "29") (name "Net-(IC3-RF1)") (class "Default")
      (node (ref "C28") (pin "2") (pinfunction "2_2") (pintype "passive"))
      (node (ref "IC3") (pin "4") (pinfunction "RF1_4") (pintype "bidirectional"))
    )
    (net (code "30") (name "Net-(IC3-RF2)") (class "Default")
      (node (ref "C36") (pin "1") (pinfunction "1_1") (pintype "passive"))
      (node (ref "IC3") (pin "15") (pinfunction "RF2_15") (pintype "bidirectional"))
    )
    (net (code "31") (name "Net-(IC3-VCC)") (class "Default")
      (node (ref "C21") (pin "2") (pinfunction "2_2") (pintype "passive"))
      (node (ref "C22") (pin "2") (pinfunction "2_2") (pintype "passive"))
      (node (ref "C23") (pin "2") (pinfunction "2_2") (pintype "passive"))
      (node (ref "C24") (pin "2") (pinfunction "2_2") (pintype "passive"))
      (node (ref "IC3") (pin "2") (pinfunction "VCC_2") (pintype "power_in"))
      (node (ref "L7") (pin "2") (pinfunction "2_2") (pintype "passive"))
    )
    (net (code "32") (name "Net-(IC5-RF_IN)") (class "Default")
      (node (ref "C55") (pin "2") (pinfunction "2_2") (pintype "passive"))
      (node (ref "IC5") (pin "1") (pinfunction "RF_IN_1") (pintype "input"))
      (node (ref "R178") (pin "1") (pinfunction "1_1") (pintype "passive"))
    )
    (net (code "33") (name "Net-(IC5-RF_OUT)") (class "Default")
      (node (ref "C29") (pin "1") (pinfunction "1_1") (pintype "passive"))
      (node (ref "IC5") (pin "3") (pinfunction "RF_OUT_3") (pintype "output"))
      (node (ref "L1") (pin "3") (pinfunction "3_3") (pintype "passive"))
      (node (ref "R178") (pin "2") (pinfunction "2_2") (pintype "passive"))
    )
    (net (code "34") (name "Net-(IC17-IN)") (class "Default")
      (node (ref "C55") (pin "1") (pinfunction "1_1") (pintype "passive"))
      (node (ref "IC17") (pin "1") (pinfunction "IN_1") (pintype "bidirectional"))
    )
    (net (code "35") (name "Net-(IC17-OUT)") (class "Default")
      (node (ref "C36") (pin "2") (pinfunction "2_2") (pintype "passive"))
      (node (ref "IC17") (pin "2") (pinfunction "OUT_2") (pintype "bidirectional"))
    )
    (net (code "36") (name "Net-(IC23-EN)") (class "Default")
      (node (ref "IC23") (pin "5") (pinfunction "EN_5") (pintype "input"))
      (node (ref "R138") (pin "2") (pinfunction "2_2") (pintype "passive"))
    )
    (net (code "37") (name "Net-(IC23-RF1)") (class "Default")
      (node (ref "C49") (pin "1") (pinfunction "1_1") (pintype "passive"))
      (node (ref "IC23") (pin "9") (pinfunction "RF1_9") (pintype "bidirectional"))
    )
    (net (code "38") (name "Net-(IC23-RF2)") (class "Default")
      (node (ref "C47") (pin "1") (pinfunction "1_1") (pintype "passive"))
      (node (ref "IC23") (pin "12") (pinfunction "RF2_12") (pintype "bidirectional"))
    )
    (net (code "39") (name "Net-(IC23-RFC)") (class "Default")
      (node (ref "C29") (pin "2") (pinfunction "2_2") (pintype "passive"))
      (node (ref "IC23") (pin "3") (pinfunction "RFC_3") (pintype "bidirectional"))
    )
    (net (code "40") (name "Net-(IC23-VDD)") (class "Default")
      (node (ref "C38") (pin "1") (pinfunction "1_1") (pintype "passive"))
      (node (ref "C39") (pin "2") (pinfunction "2_2") (pintype "passive"))
      (node (ref "C40") (pin "2") (pinfunction "2_2") (pintype "passive"))
      (node (ref "IC23") (pin "1") (pinfunction "VDD_1") (pintype "power_in"))
      (node (ref "L6") (pin "1") (pinfunction "1_1") (pintype "passive"))
    )
    (net (code "41") (name "Net-(L1-Pad1)") (class "Default")
      (node (ref "L1") (pin "1") (pinfunction "1_1") (pintype "passive"))
      (node (ref "R137") (pin "2") (pinfunction "2_2") (pintype "passive"))
    )
    (net (code "42") (name "P5V0A") (class "Default")
      (node (ref "L6") (pin "2") (pinfunction "2_2") (pintype "passive"))
      (node (ref "L7") (pin "1") (pinfunction "1_1") (pintype "passive"))
    )
    (net (code "43") (name "P7V0A") (class "Default")
      (node (ref "C12") (pin "2") (pinfunction "2_2") (pintype "passive"))
      (node (ref "C27") (pin "2") (pinfunction "2_2") (pintype "passive"))
      (node (ref "R137") (pin "1") (pinfunction "1_1") (pintype "passive"))
    )
    (net (code "44") (name "unconnected-(IC23-NC-Pad4)") (class "Default")
      (node (ref "IC23") (pin "4") (pinfunction "NC_4") (pintype "passive+no_connect"))
    )
    (net (code "45") (name "unconnected-(IC23-NC-Pad6)") (class "Default")
      (node (ref "IC23") (pin "6") (pinfunction "NC_6") (pintype "passive+no_connect"))
    )
    (net (code "46") (name "unconnected-(IC23-NC-Pad7)") (class "Default")
      (node (ref "IC23") (pin "7") (pinfunction "NC_7") (pintype "passive+no_connect"))
    )
    (net (code "47") (name "unconnected-(IC23-NC-Pad8)") (class "Default")
      (node (ref "IC23") (pin "8") (pinfunction "NC_8") (pintype "passive+no_connect"))
    )
    (net (code "48") (name "unconnected-(IC23-NC-Pad13)") (class "Default")
      (node (ref "IC23") (pin "13") (pinfunction "NC_13") (pintype "passive+no_connect"))
    )
    (net (code "49") (name "unconnected-(IC23-NC-Pad14)") (class "Default")
      (node (ref "IC23") (pin "14") (pinfunction "NC_14") (pintype "passive+no_connect"))
    )
    (net (code "50") (name "unconnected-(IC23-NC-Pad15)") (class "Default")
      (node (ref "IC23") (pin "15") (pinfunction "NC_15") (pintype "passive+no_connect"))
    )
    (net (code "51") (name "unconnected-(IC23-NC-Pad16)") (class "Default")
      (node (ref "IC23") (pin "16") (pinfunction "NC_16") (pintype "passive+no_connect"))
    )
  )
)
